# flync_node.net
KiCad netlist of a schematic drawn in EAGLE
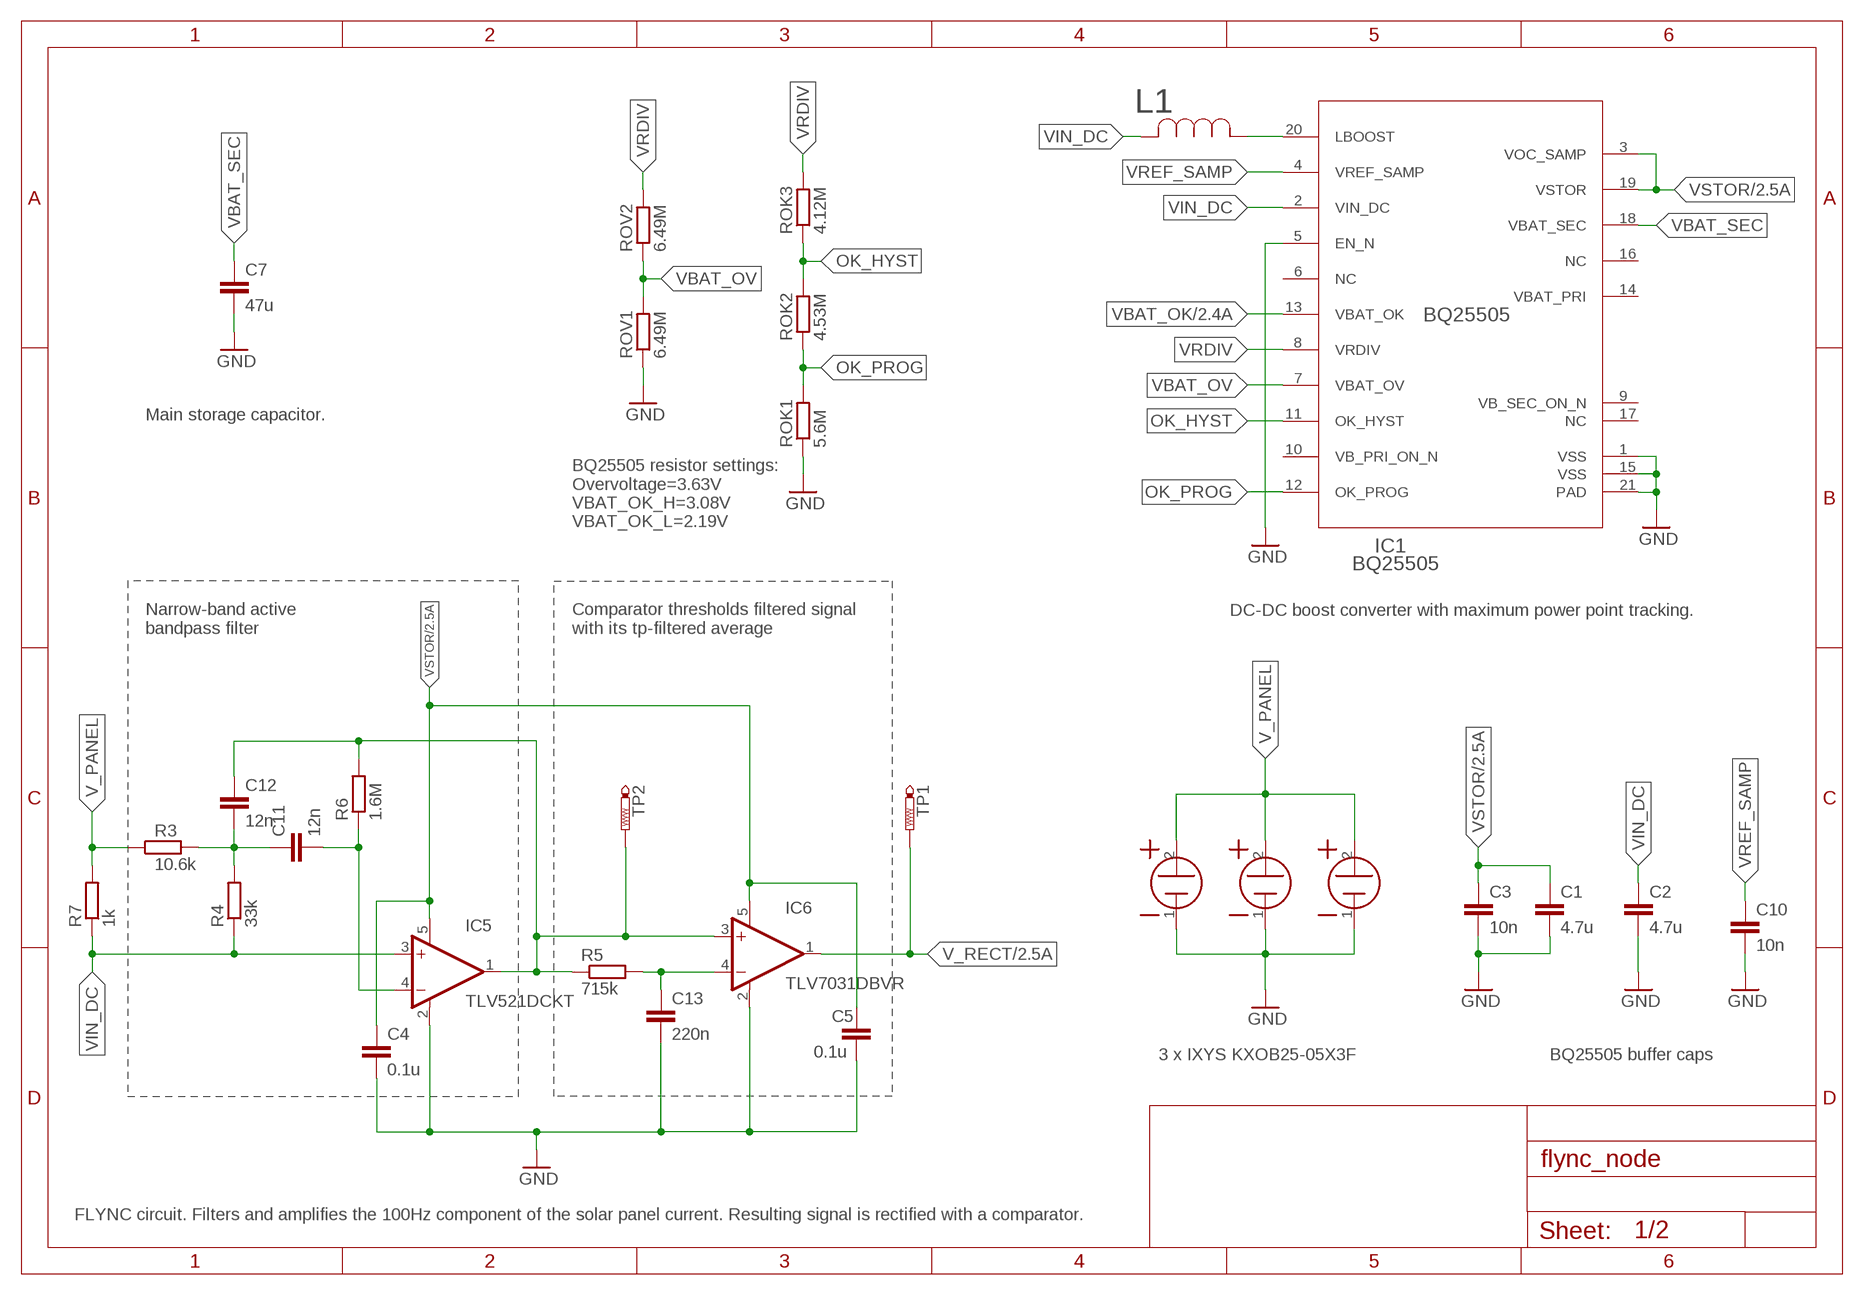
[diagram p0: schematic, sheet 1]
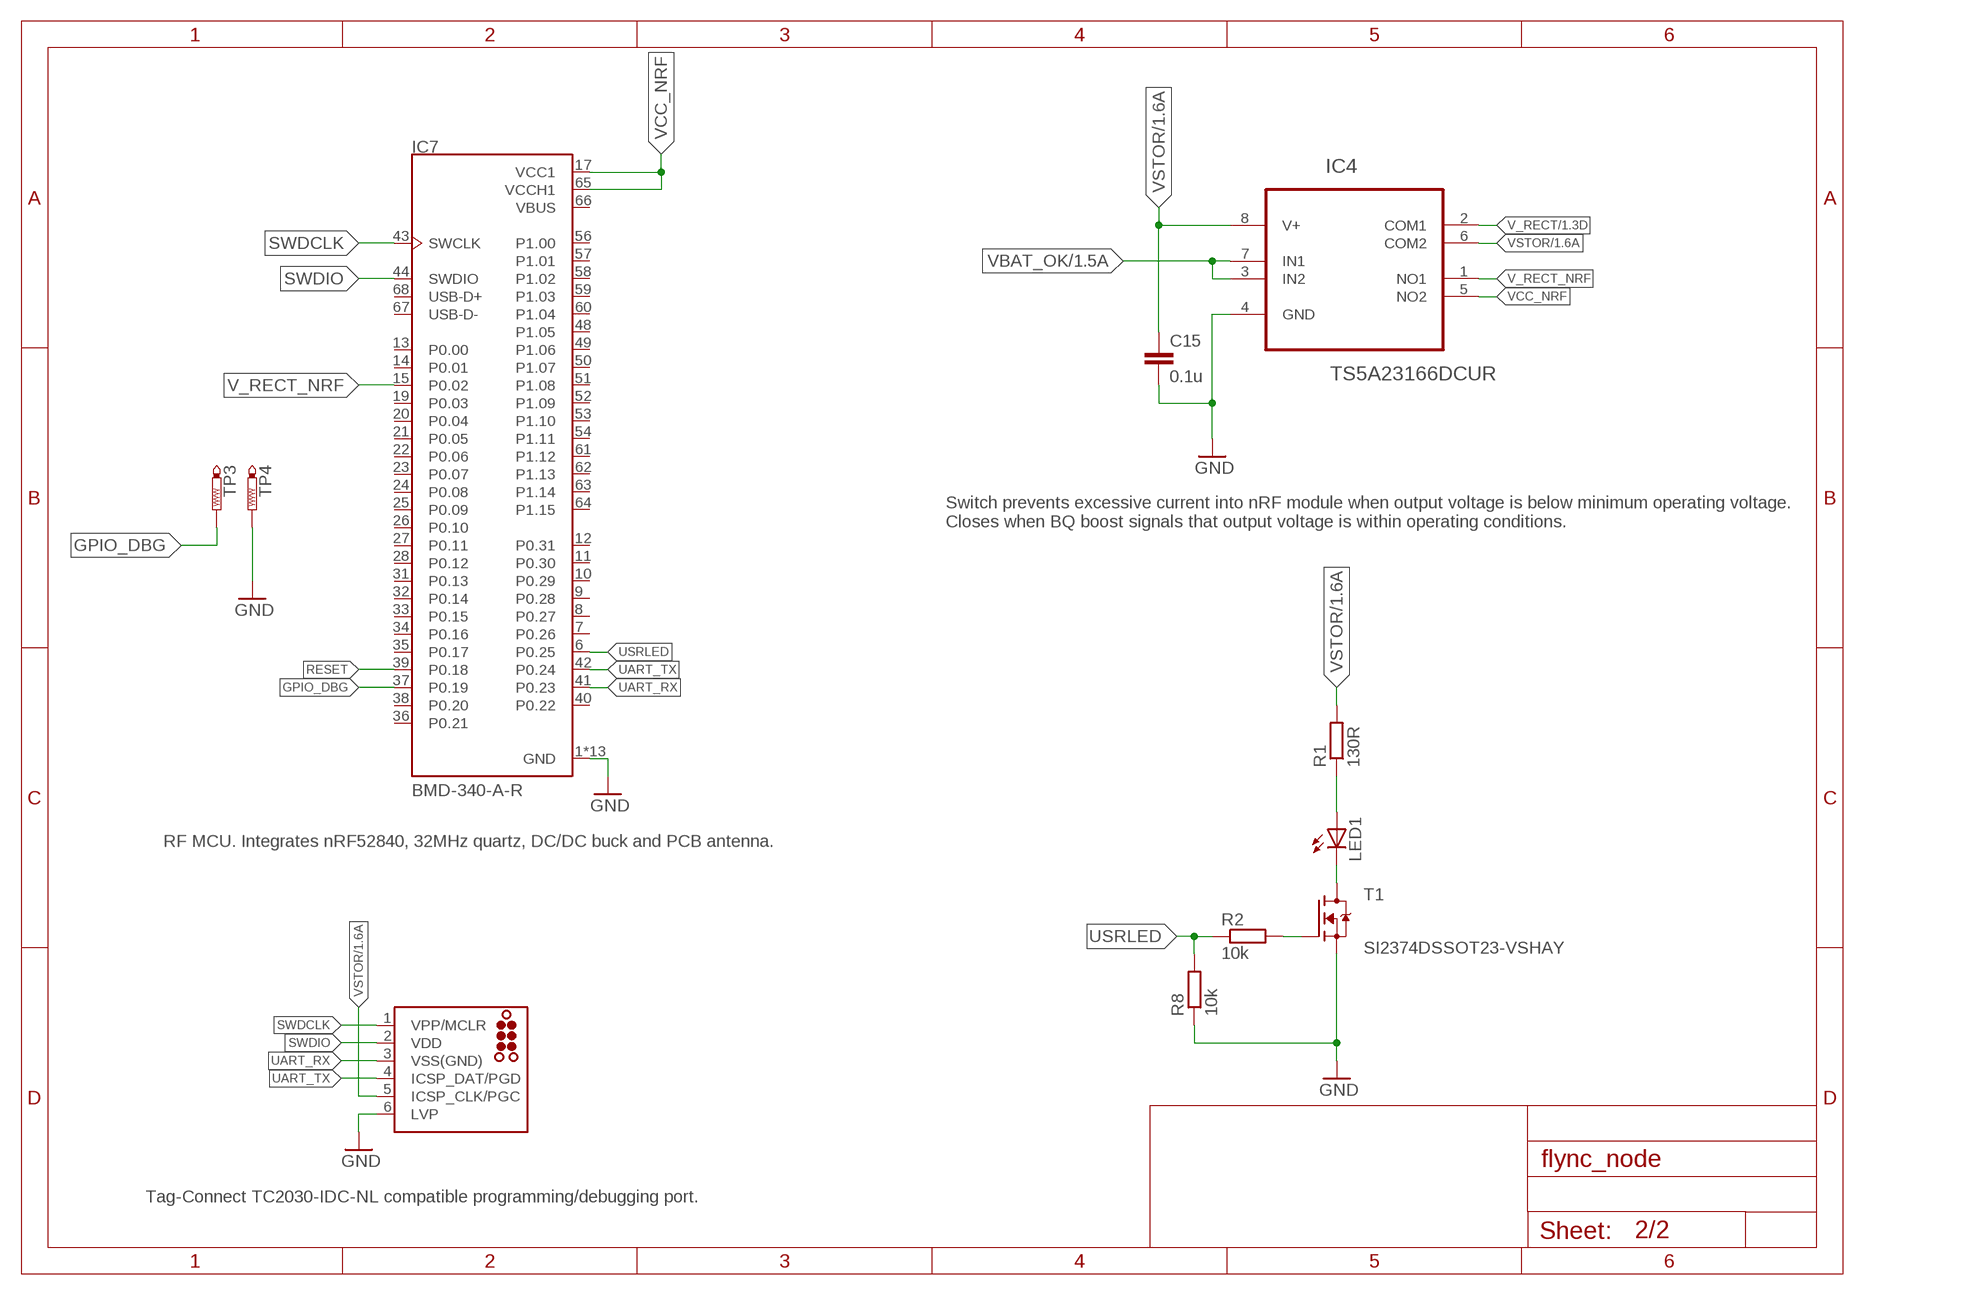
[diagram p1: schematic, sheet 2]

(export (version "E")
  (design (tool "Eeschema 10.0.6"))
  (components
    (comp (ref "C1")
      (value "4.7u")
      (footprint "eagle-import:CAPC1005X55")
      (libsource (lib "eagle-import") (part "C_SMD0402"))
    )
    (comp (ref "C2")
      (value "4.7u")
      (footprint "eagle-import:CAPC1005X55")
      (libsource (lib "eagle-import") (part "C_SMD0402"))
    )
    (comp (ref "C3")
      (value "10n")
      (footprint "eagle-import:CAPC1005X55")
      (libsource (lib "eagle-import") (part "C_SMD0402"))
    )
    (comp (ref "C4")
      (value "0.1u")
      (footprint "eagle-import:CAPC1005X55")
      (libsource (lib "eagle-import") (part "C_SMD0402"))
    )
    (comp (ref "C5")
      (value "0.1u")
      (footprint "eagle-import:CAPC1005X55")
      (libsource (lib "eagle-import") (part "C_SMD0402"))
    )
    (comp (ref "C7")
      (value "47u")
      (footprint "eagle-import:CAPC2012X145")
      (libsource (lib "eagle-import") (part "C_SMD0805"))
    )
    (comp (ref "C10")
      (value "10n")
      (footprint "eagle-import:CAPC1005X55")
      (libsource (lib "eagle-import") (part "C_SMD0402"))
    )
    (comp (ref "C11")
      (value "12n")
      (footprint "eagle-import:CAPC2012X145")
      (libsource (lib "eagle-import") (part "C_SMD0805"))
    )
    (comp (ref "C12")
      (value "12n")
      (footprint "eagle-import:CAPC2012X145")
      (libsource (lib "eagle-import") (part "C_SMD0805"))
    )
    (comp (ref "C13")
      (value "220n")
      (footprint "eagle-import:CAPC1005X55")
      (libsource (lib "eagle-import") (part "C_SMD0402"))
    )
    (comp (ref "H1")
      (value "IXYSKXOB25-05X3F")
      (footprint "eagle-import:IXYS23X8")
      (libsource (lib "eagle-import") (part "IXYSKXOB25-05X3F"))
    )
    (comp (ref "H2")
      (value "IXYSKXOB25-05X3F")
      (footprint "eagle-import:IXYS23X8")
      (libsource (lib "eagle-import") (part "IXYSKXOB25-05X3F"))
    )
    (comp (ref "H3")
      (value "IXYSKXOB25-05X3F")
      (footprint "eagle-import:IXYS23X8")
      (libsource (lib "eagle-import") (part "IXYSKXOB25-05X3F"))
    )
    (comp (ref "IC1")
      (value "BQ25505")
      (footprint "eagle-import:RGR0020A")
      (libsource (lib "eagle-import") (part "BQ25505"))
    )
    (comp (ref "IC5")
      (value "TLV521DCKT")
      (footprint "eagle-import:DCK5")
      (fields (field (name "COPYRIGHT") "Copyright (C) 2018 Accelerated Designs. All rights reserved"))
      (libsource (lib "eagle-import") (part "TLV521DCKT"))
    )
    (comp (ref "IC6")
      (value "TLV7031DBVR")
      (footprint "eagle-import:DBV5-L")
      (libsource (lib "eagle-import") (part "TLV7031DBVR"))
    )
    (comp (ref "L1")
      (value "LBR2518T220KIND1007_47N_TAI-L")
      (footprint "eagle-import:IND1007_47N_TAI-L")
      (fields (field (name "MANUFACTURER_PART_NUMBER") "LBR2518T220K"))
      (libsource (lib "eagle-import") (part "LBR2518T220KIND1007_47N_TAI-L"))
    )
    (comp (ref "R3")
      (value "10.6k")
      (footprint "eagle-import:RESC1005X40")
      (libsource (lib "eagle-import") (part "R_SMD0402"))
    )
    (comp (ref "R4")
      (value "33k")
      (footprint "eagle-import:RESC1005X40")
      (libsource (lib "eagle-import") (part "R_SMD0402"))
    )
    (comp (ref "R5")
      (value "715k")
      (footprint "eagle-import:RESC1005X40")
      (libsource (lib "eagle-import") (part "R_SMD0402"))
    )
    (comp (ref "R6")
      (value "1.6M")
      (footprint "eagle-import:RESC1005X40")
      (libsource (lib "eagle-import") (part "R_SMD0402"))
    )
    (comp (ref "R7")
      (value "1k")
      (footprint "eagle-import:RESC1608X55")
      (libsource (lib "eagle-import") (part "R_SMD0603"))
    )
    (comp (ref "ROK1")
      (value "5.6M")
      (footprint "eagle-import:RESC1005X40")
      (libsource (lib "eagle-import") (part "R_SMD0402"))
    )
    (comp (ref "ROK2")
      (value "4.53M")
      (footprint "eagle-import:RESC1005X40")
      (libsource (lib "eagle-import") (part "R_SMD0402"))
    )
    (comp (ref "ROK3")
      (value "4.12M")
      (footprint "eagle-import:RESC1005X40")
      (libsource (lib "eagle-import") (part "R_SMD0402"))
    )
    (comp (ref "ROV1")
      (value "6.49M")
      (footprint "eagle-import:RESC1005X40")
      (libsource (lib "eagle-import") (part "R_SMD0402"))
    )
    (comp (ref "ROV2")
      (value "6.49M")
      (footprint "eagle-import:RESC1005X40")
      (libsource (lib "eagle-import") (part "R_SMD0402"))
    )
    (comp (ref "TP1")
      (value "PTR1TP08R")
      (footprint "eagle-import:TP08R")
      (libsource (lib "eagle-import") (part "PTR1TP08R"))
    )
    (comp (ref "TP2")
      (value "PTR1TP08R")
      (footprint "eagle-import:TP08R")
      (libsource (lib "eagle-import") (part "PTR1TP08R"))
    )
    (comp (ref "C15")
      (value "0.1u")
      (footprint "eagle-import:CAPC1005X55")
      (libsource (lib "eagle-import") (part "C_SMD0402"))
    )
    (comp (ref "IC4")
      (value "TS5A23166DCUR")
      (footprint "eagle-import:SOP50P310X90-8N")
      (fields (field (name "MF") "Texas Instruments"))
      (libsource (lib "eagle-import") (part "TS5A23166DCUR"))
    )
    (comp (ref "IC7")
      (value "BMD-340-A-R")
      (footprint "eagle-import:RIGADO_BMD-340-A-R")
      (fields (field (name "MF") "Rigado"))
      (libsource (lib "eagle-import") (part "BMD-340-A-R"))
    )
    (comp (ref "J1")
      (value "TC2030-MCP-NL")
      (footprint "eagle-import:TC2030-MCP-NL")
      (libsource (lib "eagle-import") (part "TC2030-MCP-NL"))
    )
    (comp (ref "LED1")
      (value "598-8130-107FLED_0805")
      (footprint "eagle-import:LEDC2012X75")
      (libsource (lib "eagle-import") (part "598-8130-107FLED_0805"))
    )
    (comp (ref "R1")
      (value "130R")
      (footprint "eagle-import:RESC1608X55")
      (libsource (lib "eagle-import") (part "R_SMD0603"))
    )
    (comp (ref "R2")
      (value "10k")
      (footprint "eagle-import:RESC1005X40")
      (libsource (lib "eagle-import") (part "R_SMD0402"))
    )
    (comp (ref "R8")
      (value "10k")
      (footprint "eagle-import:RESC1005X40")
      (libsource (lib "eagle-import") (part "R_SMD0402"))
    )
    (comp (ref "T1")
      (value "SI2374DSSOT23-VSHAY")
      (footprint "eagle-import:SOT95P237X112-3")
      (libsource (lib "eagle-import") (part "SI2374DSSOT23-VSHAY"))
    )
    (comp (ref "TP3")
      (value "PTR1TP16SQ")
      (footprint "eagle-import:TP16SQ")
      (libsource (lib "eagle-import") (part "PTR1TP16SQ"))
    )
    (comp (ref "TP4")
      (value "PTR1TP16SQ")
      (footprint "eagle-import:TP16SQ")
      (libsource (lib "eagle-import") (part "PTR1TP16SQ"))
    )
  )
  (nets
    (net (code "1") (name "GND") (class "Default")
      (node (ref "C1") (pin "2") (pinfunction "2_2") (pintype "passive"))
      (node (ref "C10") (pin "2") (pinfunction "2_2") (pintype "passive"))
      (node (ref "C13") (pin "2") (pinfunction "2_2") (pintype "passive"))
      (node (ref "C15") (pin "2") (pinfunction "2_2") (pintype "passive"))
      (node (ref "C2") (pin "2") (pinfunction "2_2") (pintype "passive"))
      (node (ref "C3") (pin "2") (pinfunction "2_2") (pintype "passive"))
      (node (ref "C4") (pin "2") (pinfunction "2_2") (pintype "passive"))
      (node (ref "C5") (pin "2") (pinfunction "2_2") (pintype "passive"))
      (node (ref "C7") (pin "2") (pinfunction "2_2") (pintype "passive"))
      (node (ref "H1") (pin "1") (pinfunction "P$1_1") (pintype "power_in"))
      (node (ref "H2") (pin "1") (pinfunction "P$1_1") (pintype "power_in"))
      (node (ref "H3") (pin "1") (pinfunction "P$1_1") (pintype "power_in"))
      (node (ref "IC1") (pin "1") (pinfunction "VSS_1") (pintype "power_in"))
      (node (ref "IC1") (pin "15") (pinfunction "VSS_15") (pintype "power_in"))
      (node (ref "IC1") (pin "21") (pinfunction "PAD_21") (pintype "power_in"))
      (node (ref "IC1") (pin "5") (pinfunction "EN_N_5") (pintype "input"))
      (node (ref "IC4") (pin "4") (pinfunction "GND_4") (pintype "passive"))
      (node (ref "IC5") (pin "2") (pinfunction "V-_2") (pintype "power_in"))
      (node (ref "IC6") (pin "2") (pinfunction "V-_2") (pintype "power_in"))
      (node (ref "IC7") (pin "1") (pinfunction "GND_1") (pintype "power_in"))
      (node (ref "IC7") (pin "16") (pinfunction "GND_16") (pintype "power_in"))
      (node (ref "IC7") (pin "18") (pinfunction "GND_18") (pintype "power_in"))
      (node (ref "IC7") (pin "2") (pinfunction "GND_2") (pintype "power_in"))
      (node (ref "IC7") (pin "29") (pinfunction "GND_29") (pintype "power_in"))
      (node (ref "IC7") (pin "3") (pinfunction "GND_3") (pintype "power_in"))
      (node (ref "IC7") (pin "30") (pinfunction "GND_30") (pintype "power_in"))
      (node (ref "IC7") (pin "4") (pinfunction "GND_4") (pintype "power_in"))
      (node (ref "IC7") (pin "45") (pinfunction "GND_45") (pintype "power_in"))
      (node (ref "IC7") (pin "46") (pinfunction "GND_46") (pintype "power_in"))
      (node (ref "IC7") (pin "47") (pinfunction "GND_47") (pintype "power_in"))
      (node (ref "IC7") (pin "5") (pinfunction "GND_5") (pintype "power_in"))
      (node (ref "IC7") (pin "55") (pinfunction "GND_55") (pintype "power_in"))
      (node (ref "J1") (pin "6") (pinfunction "LVP_6") (pintype "bidirectional"))
      (node (ref "R8") (pin "1") (pinfunction "1_1") (pintype "passive"))
      (node (ref "ROK1") (pin "1") (pinfunction "1_1") (pintype "passive"))
      (node (ref "ROV1") (pin "1") (pinfunction "1_1") (pintype "passive"))
      (node (ref "T1") (pin "2") (pinfunction "S_2") (pintype "passive"))
      (node (ref "TP4") (pin "TP") (pinfunction "TP_TP") (pintype "input"))
    )
    (net (code "2") (name "GPIO_DBG") (class "Default")
      (node (ref "IC7") (pin "37") (pinfunction "P0.19_37") (pintype "bidirectional"))
      (node (ref "TP3") (pin "TP") (pinfunction "TP_TP") (pintype "input"))
    )
    (net (code "3") (name "Net-(C11-Pad1)") (class "Default")
      (node (ref "C11") (pin "1") (pinfunction "1_1") (pintype "passive"))
      (node (ref "C12") (pin "2") (pinfunction "2_2") (pintype "passive"))
      (node (ref "R3") (pin "2") (pinfunction "2_2") (pintype "passive"))
      (node (ref "R4") (pin "2") (pinfunction "2_2") (pintype "passive"))
    )
    (net (code "4") (name "Net-(IC1-LBOOST)") (class "Default")
      (node (ref "IC1") (pin "20") (pinfunction "LBOOST_20") (pintype "input"))
      (node (ref "L1") (pin "1") (pinfunction "1_1") (pintype "passive"))
    )
    (net (code "5") (name "Net-(IC5--IN)") (class "Default")
      (node (ref "C11") (pin "2") (pinfunction "2_2") (pintype "passive"))
      (node (ref "IC5") (pin "4") (pinfunction "-IN_4") (pintype "input"))
      (node (ref "R6") (pin "1") (pinfunction "1_1") (pintype "passive"))
    )
    (net (code "6") (name "Net-(IC5-OUT)") (class "Default")
      (node (ref "C12") (pin "1") (pinfunction "1_1") (pintype "passive"))
      (node (ref "IC5") (pin "1") (pinfunction "OUT_1") (pintype "output"))
      (node (ref "IC6") (pin "3") (pinfunction "+IN_3") (pintype "input"))
      (node (ref "R5") (pin "1") (pinfunction "1_1") (pintype "passive"))
      (node (ref "R6") (pin "2") (pinfunction "2_2") (pintype "passive"))
      (node (ref "TP2") (pin "TP") (pinfunction "TP_TP") (pintype "input"))
    )
    (net (code "7") (name "Net-(IC6--IN)") (class "Default")
      (node (ref "C13") (pin "1") (pinfunction "1_1") (pintype "passive"))
      (node (ref "IC6") (pin "4") (pinfunction "-IN_4") (pintype "input"))
      (node (ref "R5") (pin "2") (pinfunction "2_2") (pintype "passive"))
    )
    (net (code "8") (name "Net-(LED1-A)") (class "Default")
      (node (ref "LED1") (pin "2") (pinfunction "A_2") (pintype "passive"))
      (node (ref "R1") (pin "1") (pinfunction "1_1") (pintype "passive"))
    )
    (net (code "9") (name "Net-(LED1-C)") (class "Default")
      (node (ref "LED1") (pin "1") (pinfunction "C_1") (pintype "passive"))
      (node (ref "T1") (pin "3") (pinfunction "D_3") (pintype "passive"))
    )
    (net (code "10") (name "Net-(T1-G)") (class "Default")
      (node (ref "R2") (pin "2") (pinfunction "2_2") (pintype "passive"))
      (node (ref "T1") (pin "1") (pinfunction "G_1") (pintype "passive"))
    )
    (net (code "11") (name "OK_HYST") (class "Default")
      (node (ref "IC1") (pin "11") (pinfunction "OK_HYST_11") (pintype "input"))
      (node (ref "ROK2") (pin "2") (pinfunction "2_2") (pintype "passive"))
      (node (ref "ROK3") (pin "1") (pinfunction "1_1") (pintype "passive"))
    )
    (net (code "12") (name "OK_PROG") (class "Default")
      (node (ref "IC1") (pin "12") (pinfunction "OK_PROG_12") (pintype "input"))
      (node (ref "ROK1") (pin "2") (pinfunction "2_2") (pintype "passive"))
      (node (ref "ROK2") (pin "1") (pinfunction "1_1") (pintype "passive"))
    )
    (net (code "13") (name "RESET") (class "Default")
      (node (ref "IC7") (pin "39") (pinfunction "P0.18_39") (pintype "bidirectional"))
    )
    (net (code "14") (name "SWDCLK") (class "Default")
      (node (ref "IC7") (pin "43") (pinfunction "SWCLK_43") (pintype "input"))
      (node (ref "J1") (pin "1") (pinfunction "VPP/MCLR_1") (pintype "passive"))
    )
    (net (code "15") (name "SWDIO") (class "Default")
      (node (ref "IC7") (pin "44") (pinfunction "SWDIO_44") (pintype "bidirectional"))
      (node (ref "J1") (pin "2") (pinfunction "VDD_2") (pintype "power_in"))
    )
    (net (code "16") (name "UART_RX") (class "Default")
      (node (ref "IC7") (pin "41") (pinfunction "P0.23_41") (pintype "bidirectional"))
      (node (ref "J1") (pin "3") (pinfunction "VSS(GND)_3") (pintype "power_in"))
    )
    (net (code "17") (name "UART_TX") (class "Default")
      (node (ref "IC7") (pin "42") (pinfunction "P0.24_42") (pintype "bidirectional"))
      (node (ref "J1") (pin "4") (pinfunction "ICSP_DAT/PGD_4") (pintype "bidirectional"))
    )
    (net (code "18") (name "USRLED") (class "Default")
      (node (ref "IC7") (pin "6") (pinfunction "P0.25_6") (pintype "bidirectional"))
      (node (ref "R2") (pin "1") (pinfunction "1_1") (pintype "passive"))
      (node (ref "R8") (pin "2") (pinfunction "2_2") (pintype "passive"))
    )
    (net (code "19") (name "VBAT_OK") (class "Default")
      (node (ref "IC1") (pin "13") (pinfunction "VBAT_OK_13") (pintype "output"))
      (node (ref "IC4") (pin "3") (pinfunction "IN2_3") (pintype "input"))
      (node (ref "IC4") (pin "7") (pinfunction "IN1_7") (pintype "input"))
    )
    (net (code "20") (name "VBAT_OV") (class "Default")
      (node (ref "IC1") (pin "7") (pinfunction "VBAT_OV_7") (pintype "input"))
      (node (ref "ROV1") (pin "2") (pinfunction "2_2") (pintype "passive"))
      (node (ref "ROV2") (pin "1") (pinfunction "1_1") (pintype "passive"))
    )
    (net (code "21") (name "VBAT_PRI") (class "Default")
      (node (ref "IC1") (pin "14") (pinfunction "VBAT_PRI_14") (pintype "power_in"))
    )
    (net (code "22") (name "VBAT_SEC") (class "Default")
      (node (ref "C7") (pin "1") (pinfunction "1_1") (pintype "passive"))
      (node (ref "IC1") (pin "18") (pinfunction "VBAT_SEC_18") (pintype "power_in"))
    )
    (net (code "23") (name "VBUS") (class "Default")
      (node (ref "IC7") (pin "66") (pinfunction "VBUS_66") (pintype "power_in"))
    )
    (net (code "24") (name "VB_SEC_ON_N") (class "Default")
      (node (ref "IC1") (pin "9") (pinfunction "VB_SEC_ON_N_9") (pintype "power_in"))
    )
    (net (code "25") (name "VCC_NRF") (class "Default")
      (node (ref "IC4") (pin "5") (pinfunction "NO2_5") (pintype "bidirectional"))
      (node (ref "IC7") (pin "17") (pinfunction "VCC1_17") (pintype "power_in"))
      (node (ref "IC7") (pin "65") (pinfunction "VCCH1_65") (pintype "power_in"))
    )
    (net (code "26") (name "VIN_DC") (class "Default")
      (node (ref "C2") (pin "1") (pinfunction "1_1") (pintype "passive"))
      (node (ref "IC1") (pin "2") (pinfunction "VIN_DC_2") (pintype "power_in"))
      (node (ref "IC5") (pin "3") (pinfunction "+IN_3") (pintype "input"))
      (node (ref "L1") (pin "2") (pinfunction "2_2") (pintype "passive"))
      (node (ref "R4") (pin "1") (pinfunction "1_1") (pintype "passive"))
      (node (ref "R7") (pin "1") (pinfunction "1_1") (pintype "passive"))
    )
    (net (code "27") (name "VRDIV") (class "Default")
      (node (ref "IC1") (pin "8") (pinfunction "VRDIV_8") (pintype "output"))
      (node (ref "ROK3") (pin "2") (pinfunction "2_2") (pintype "passive"))
      (node (ref "ROV2") (pin "2") (pinfunction "2_2") (pintype "passive"))
    )
    (net (code "28") (name "VREF_SAMP") (class "Default")
      (node (ref "C10") (pin "1") (pinfunction "1_1") (pintype "passive"))
      (node (ref "IC1") (pin "4") (pinfunction "VREF_SAMP_4") (pintype "input"))
    )
    (net (code "29") (name "VSTOR") (class "Default")
      (node (ref "C1") (pin "1") (pinfunction "1_1") (pintype "passive"))
      (node (ref "C15") (pin "1") (pinfunction "1_1") (pintype "passive"))
      (node (ref "C3") (pin "1") (pinfunction "1_1") (pintype "passive"))
      (node (ref "C4") (pin "1") (pinfunction "1_1") (pintype "passive"))
      (node (ref "C5") (pin "1") (pinfunction "1_1") (pintype "passive"))
      (node (ref "IC1") (pin "19") (pinfunction "VSTOR_19") (pintype "power_in"))
      (node (ref "IC1") (pin "3") (pinfunction "VOC_SAMP_3") (pintype "input"))
      (node (ref "IC4") (pin "6") (pinfunction "COM2_6") (pintype "bidirectional"))
      (node (ref "IC4") (pin "8") (pinfunction "V+_8") (pintype "power_in"))
      (node (ref "IC5") (pin "5") (pinfunction "V+_5") (pintype "power_in"))
      (node (ref "IC6") (pin "5") (pinfunction "V+_5") (pintype "power_in"))
      (node (ref "J1") (pin "5") (pinfunction "ICSP_CLK/PGC_5") (pintype "output"))
      (node (ref "R1") (pin "2") (pinfunction "2_2") (pintype "passive"))
    )
    (net (code "30") (name "V_PANEL") (class "Default")
      (node (ref "H1") (pin "2") (pinfunction "P$2_2") (pintype "power_in"))
      (node (ref "H2") (pin "2") (pinfunction "P$2_2") (pintype "power_in"))
      (node (ref "H3") (pin "2") (pinfunction "P$2_2") (pintype "power_in"))
      (node (ref "R3") (pin "1") (pinfunction "1_1") (pintype "passive"))
      (node (ref "R7") (pin "2") (pinfunction "2_2") (pintype "passive"))
    )
    (net (code "31") (name "V_RECT") (class "Default")
      (node (ref "IC4") (pin "2") (pinfunction "COM1_2") (pintype "bidirectional"))
      (node (ref "IC6") (pin "1") (pinfunction "OUT_1") (pintype "output"))
      (node (ref "TP1") (pin "TP") (pinfunction "TP_TP") (pintype "input"))
    )
    (net (code "32") (name "V_RECT_NRF") (class "Default")
      (node (ref "IC4") (pin "1") (pinfunction "NO1_1") (pintype "bidirectional"))
      (node (ref "IC7") (pin "15") (pinfunction "P0.02_15") (pintype "bidirectional"))
    )
    (net (code "33") (name "unconnected-(IC1-NC-Pad6)") (class "Default")
      (node (ref "IC1") (pin "6") (pinfunction "NC_6") (pintype "no_connect"))
    )
    (net (code "34") (name "unconnected-(IC1-NC-Pad16)") (class "Default")
      (node (ref "IC1") (pin "16") (pinfunction "NC_16") (pintype "no_connect"))
    )
    (net (code "35") (name "unconnected-(IC1-NC-Pad17)") (class "Default")
      (node (ref "IC1") (pin "17") (pinfunction "NC_17") (pintype "no_connect"))
    )
    (net (code "36") (name "unconnected-(IC1-VB_PRI_ON_N-Pad10)") (class "Default")
      (node (ref "IC1") (pin "10") (pinfunction "VB_PRI_ON_N_10") (pintype "output"))
    )
    (net (code "37") (name "unconnected-(IC7-P0.00-Pad13)") (class "Default")
      (node (ref "IC7") (pin "13") (pinfunction "P0.00_13") (pintype "bidirectional"))
    )
    (net (code "38") (name "unconnected-(IC7-P0.01-Pad14)") (class "Default")
      (node (ref "IC7") (pin "14") (pinfunction "P0.01_14") (pintype "bidirectional"))
    )
    (net (code "39") (name "unconnected-(IC7-P0.03-Pad19)") (class "Default")
      (node (ref "IC7") (pin "19") (pinfunction "P0.03_19") (pintype "bidirectional"))
    )
    (net (code "40") (name "unconnected-(IC7-P0.04-Pad20)") (class "Default")
      (node (ref "IC7") (pin "20") (pinfunction "P0.04_20") (pintype "bidirectional"))
    )
    (net (code "41") (name "unconnected-(IC7-P0.05-Pad21)") (class "Default")
      (node (ref "IC7") (pin "21") (pinfunction "P0.05_21") (pintype "bidirectional"))
    )
    (net (code "42") (name "unconnected-(IC7-P0.06-Pad22)") (class "Default")
      (node (ref "IC7") (pin "22") (pinfunction "P0.06_22") (pintype "bidirectional"))
    )
    (net (code "43") (name "unconnected-(IC7-P0.07-Pad23)") (class "Default")
      (node (ref "IC7") (pin "23") (pinfunction "P0.07_23") (pintype "bidirectional"))
    )
    (net (code "44") (name "unconnected-(IC7-P0.08-Pad24)") (class "Default")
      (node (ref "IC7") (pin "24") (pinfunction "P0.08_24") (pintype "bidirectional"))
    )
    (net (code "45") (name "unconnected-(IC7-P0.09-Pad25)") (class "Default")
      (node (ref "IC7") (pin "25") (pinfunction "P0.09_25") (pintype "bidirectional"))
    )
    (net (code "46") (name "unconnected-(IC7-P0.10-Pad26)") (class "Default")
      (node (ref "IC7") (pin "26") (pinfunction "P0.10_26") (pintype "bidirectional"))
    )
    (net (code "47") (name "unconnected-(IC7-P0.11-Pad27)") (class "Default")
      (node (ref "IC7") (pin "27") (pinfunction "P0.11_27") (pintype "bidirectional"))
    )
    (net (code "48") (name "unconnected-(IC7-P0.12-Pad28)") (class "Default")
      (node (ref "IC7") (pin "28") (pinfunction "P0.12_28") (pintype "bidirectional"))
    )
    (net (code "49") (name "unconnected-(IC7-P0.13-Pad31)") (class "Default")
      (node (ref "IC7") (pin "31") (pinfunction "P0.13_31") (pintype "bidirectional"))
    )
    (net (code "50") (name "unconnected-(IC7-P0.14-Pad32)") (class "Default")
      (node (ref "IC7") (pin "32") (pinfunction "P0.14_32") (pintype "bidirectional"))
    )
    (net (code "51") (name "unconnected-(IC7-P0.15-Pad33)") (class "Default")
      (node (ref "IC7") (pin "33") (pinfunction "P0.15_33") (pintype "bidirectional"))
    )
    (net (code "52") (name "unconnected-(IC7-P0.16-Pad34)") (class "Default")
      (node (ref "IC7") (pin "34") (pinfunction "P0.16_34") (pintype "bidirectional"))
    )
    (net (code "53") (name "unconnected-(IC7-P0.17-Pad35)") (class "Default")
      (node (ref "IC7") (pin "35") (pinfunction "P0.17_35") (pintype "bidirectional"))
    )
    (net (code "54") (name "unconnected-(IC7-P0.20-Pad38)") (class "Default")
      (node (ref "IC7") (pin "38") (pinfunction "P0.20_38") (pintype "bidirectional"))
    )
    (net (code "55") (name "unconnected-(IC7-P0.21-Pad36)") (class "Default")
      (node (ref "IC7") (pin "36") (pinfunction "P0.21_36") (pintype "bidirectional"))
    )
    (net (code "56") (name "unconnected-(IC7-P0.22-Pad40)") (class "Default")
      (node (ref "IC7") (pin "40") (pinfunction "P0.22_40") (pintype "bidirectional"))
    )
    (net (code "57") (name "unconnected-(IC7-P0.26-Pad7)") (class "Default")
      (node (ref "IC7") (pin "7") (pinfunction "P0.26_7") (pintype "bidirectional"))
    )
    (net (code "58") (name "unconnected-(IC7-P0.27-Pad8)") (class "Default")
      (node (ref "IC7") (pin "8") (pinfunction "P0.27_8") (pintype "bidirectional"))
    )
    (net (code "59") (name "unconnected-(IC7-P0.28-Pad9)") (class "Default")
      (node (ref "IC7") (pin "9") (pinfunction "P0.28_9") (pintype "bidirectional"))
    )
    (net (code "60") (name "unconnected-(IC7-P0.29-Pad10)") (class "Default")
      (node (ref "IC7") (pin "10") (pinfunction "P0.29_10") (pintype "bidirectional"))
    )
    (net (code "61") (name "unconnected-(IC7-P0.30-Pad11)") (class "Default")
      (node (ref "IC7") (pin "11") (pinfunction "P0.30_11") (pintype "bidirectional"))
    )
    (net (code "62") (name "unconnected-(IC7-P0.31-Pad12)") (class "Default")
      (node (ref "IC7") (pin "12") (pinfunction "P0.31_12") (pintype "bidirectional"))
    )
    (net (code "63") (name "unconnected-(IC7-P1.00-Pad56)") (class "Default")
      (node (ref "IC7") (pin "56") (pinfunction "P1.00_56") (pintype "bidirectional"))
    )
    (net (code "64") (name "unconnected-(IC7-P1.01-Pad57)") (class "Default")
      (node (ref "IC7") (pin "57") (pinfunction "P1.01_57") (pintype "bidirectional"))
    )
    (net (code "65") (name "unconnected-(IC7-P1.02-Pad58)") (class "Default")
      (node (ref "IC7") (pin "58") (pinfunction "P1.02_58") (pintype "bidirectional"))
    )
    (net (code "66") (name "unconnected-(IC7-P1.03-Pad59)") (class "Default")
      (node (ref "IC7") (pin "59") (pinfunction "P1.03_59") (pintype "bidirectional"))
    )
    (net (code "67") (name "unconnected-(IC7-P1.04-Pad60)") (class "Default")
      (node (ref "IC7") (pin "60") (pinfunction "P1.04_60") (pintype "bidirectional"))
    )
    (net (code "68") (name "unconnected-(IC7-P1.05-Pad48)") (class "Default")
      (node (ref "IC7") (pin "48") (pinfunction "P1.05_48") (pintype "bidirectional"))
    )
    (net (code "69") (name "unconnected-(IC7-P1.06-Pad49)") (class "Default")
      (node (ref "IC7") (pin "49") (pinfunction "P1.06_49") (pintype "bidirectional"))
    )
    (net (code "70") (name "unconnected-(IC7-P1.07-Pad50)") (class "Default")
      (node (ref "IC7") (pin "50") (pinfunction "P1.07_50") (pintype "bidirectional"))
    )
    (net (code "71") (name "unconnected-(IC7-P1.08-Pad51)") (class "Default")
      (node (ref "IC7") (pin "51") (pinfunction "P1.08_51") (pintype "bidirectional"))
    )
    (net (code "72") (name "unconnected-(IC7-P1.09-Pad52)") (class "Default")
      (node (ref "IC7") (pin "52") (pinfunction "P1.09_52") (pintype "bidirectional"))
    )
    (net (code "73") (name "unconnected-(IC7-P1.10-Pad53)") (class "Default")
      (node (ref "IC7") (pin "53") (pinfunction "P1.10_53") (pintype "bidirectional"))
    )
    (net (code "74") (name "unconnected-(IC7-P1.11-Pad54)") (class "Default")
      (node (ref "IC7") (pin "54") (pinfunction "P1.11_54") (pintype "bidirectional"))
    )
    (net (code "75") (name "unconnected-(IC7-P1.12-Pad61)") (class "Default")
      (node (ref "IC7") (pin "61") (pinfunction "P1.12_61") (pintype "bidirectional"))
    )
    (net (code "76") (name "unconnected-(IC7-P1.13-Pad62)") (class "Default")
      (node (ref "IC7") (pin "62") (pinfunction "P1.13_62") (pintype "bidirectional"))
    )
    (net (code "77") (name "unconnected-(IC7-P1.14-Pad63)") (class "Default")
      (node (ref "IC7") (pin "63") (pinfunction "P1.14_63") (pintype "bidirectional"))
    )
    (net (code "78") (name "unconnected-(IC7-P1.15-Pad64)") (class "Default")
      (node (ref "IC7") (pin "64") (pinfunction "P1.15_64") (pintype "bidirectional"))
    )
    (net (code "79") (name "unconnected-(IC7-USB-D+-Pad68)") (class "Default")
      (node (ref "IC7") (pin "68") (pinfunction "USB-D+_68") (pintype "bidirectional"))
    )
    (net (code "80") (name "unconnected-(IC7-USB-D--Pad67)") (class "Default")
      (node (ref "IC7") (pin "67") (pinfunction "USB-D-_67") (pintype "bidirectional"))
    )
  )
)
